# Tiny84_board.net
KiCad netlist of a schematic drawn in EAGLE
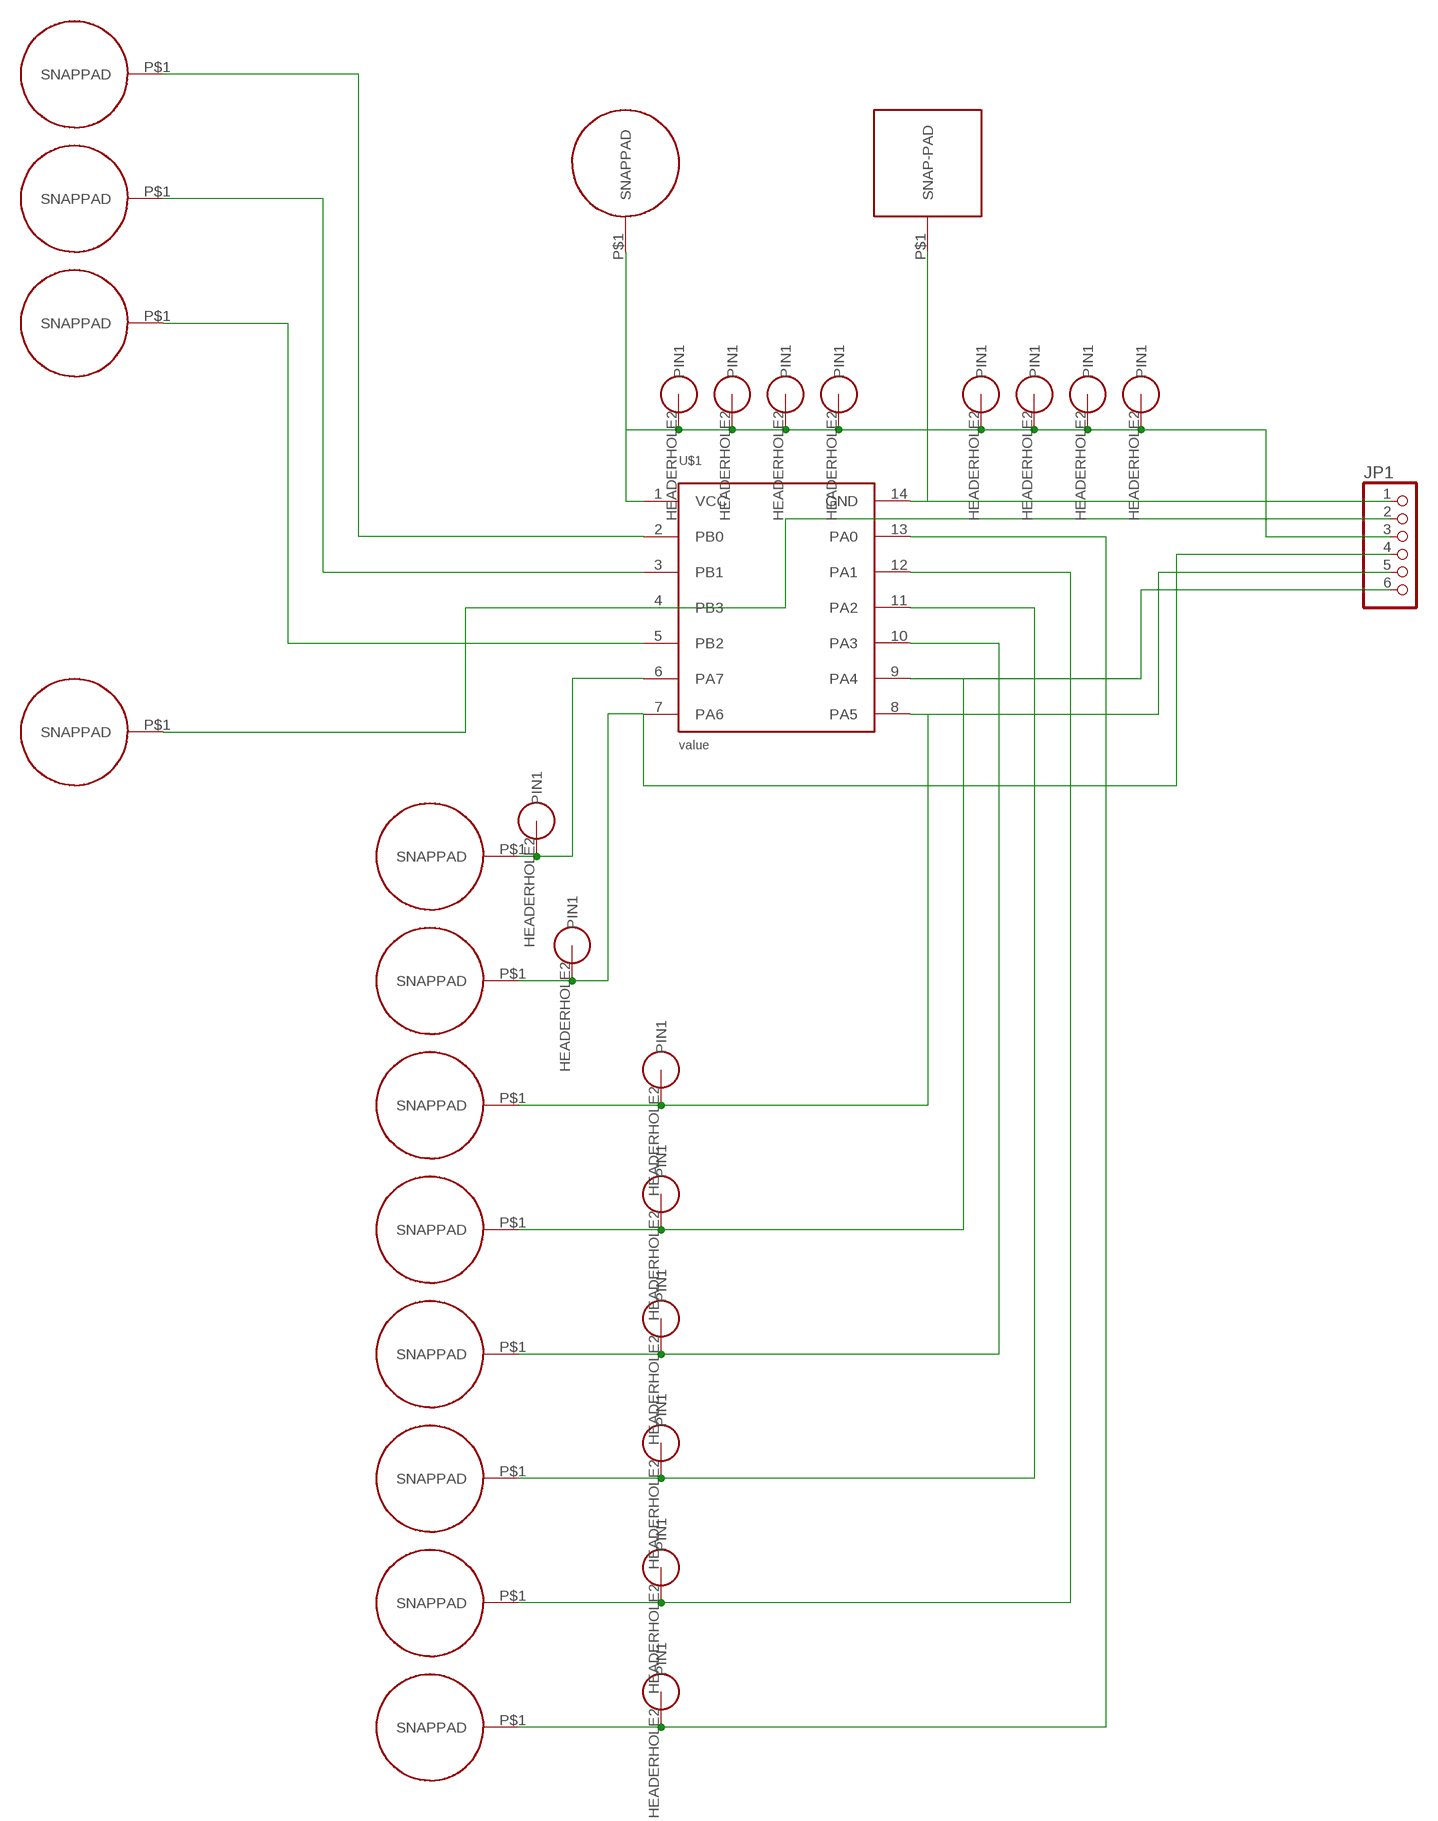
[diagram p0: schematic, sheet 1]

(export (version "E")
  (design (tool "Eeschema 10.0.6"))
  (components
    (comp (ref "JP1")
      (value "PINHD-1X6/90")
      (footprint "eagle-import:1X06_90")
      (libsource (lib "eagle-import") (part "PINHD-1X6/90"))
    )
    (comp (ref "U$1")
      (value "ATTINY84")
      (footprint "eagle-import:SOIC14")
      (libsource (lib "eagle-import") (part "ATTINY84"))
    )
    (comp (ref "U$2")
      (value "SNAP-PAD_7MM_ROUND")
      (footprint "eagle-import:SNAP-PAD_7MM_RD")
      (libsource (lib "eagle-import") (part "SNAP-PAD_7MM_ROUND"))
    )
    (comp (ref "U$3")
      (value "SNAP-PAD_7MM_ROUND")
      (footprint "eagle-import:SNAP-PAD_7MM_RD")
      (libsource (lib "eagle-import") (part "SNAP-PAD_7MM_ROUND"))
    )
    (comp (ref "U$4")
      (value "SNAP-PAD_7MM_ROUND")
      (footprint "eagle-import:SNAP-PAD_7MM_RD")
      (libsource (lib "eagle-import") (part "SNAP-PAD_7MM_ROUND"))
    )
    (comp (ref "U$5")
      (value "SNAP-PAD_7MM_ROUND")
      (footprint "eagle-import:SNAP-PAD_7MM_RD")
      (libsource (lib "eagle-import") (part "SNAP-PAD_7MM_ROUND"))
    )
    (comp (ref "U$6")
      (value "SNAP-PAD_7MM_ROUND")
      (footprint "eagle-import:SNAP-PAD_7MM_RD")
      (libsource (lib "eagle-import") (part "SNAP-PAD_7MM_ROUND"))
    )
    (comp (ref "U$7")
      (value "SNAP-PAD_7MM_ROUND")
      (footprint "eagle-import:SNAP-PAD_7MM_RD")
      (libsource (lib "eagle-import") (part "SNAP-PAD_7MM_ROUND"))
    )
    (comp (ref "U$8")
      (value "SNAP-PAD_7MM_ROUND")
      (footprint "eagle-import:SNAP-PAD_7MM_RD")
      (libsource (lib "eagle-import") (part "SNAP-PAD_7MM_ROUND"))
    )
    (comp (ref "U$9")
      (value "SNAP-PAD_7MM_ROUND")
      (footprint "eagle-import:SNAP-PAD_7MM_RD")
      (libsource (lib "eagle-import") (part "SNAP-PAD_7MM_ROUND"))
    )
    (comp (ref "U$10")
      (value "SNAP-PAD_7MM_ROUND")
      (footprint "eagle-import:SNAP-PAD_7MM_RD")
      (libsource (lib "eagle-import") (part "SNAP-PAD_7MM_ROUND"))
    )
    (comp (ref "U$11")
      (value "SNAP-PAD_7MM_ROUND")
      (footprint "eagle-import:SNAP-PAD_7MM_RD")
      (libsource (lib "eagle-import") (part "SNAP-PAD_7MM_ROUND"))
    )
    (comp (ref "U$12")
      (value "SNAP-PAD_7MM_ROUND")
      (footprint "eagle-import:SNAP-PAD_7MM_RD")
      (libsource (lib "eagle-import") (part "SNAP-PAD_7MM_ROUND"))
    )
    (comp (ref "U$13")
      (value "SNAP-PAD_7MM_ROUND")
      (footprint "eagle-import:SNAP-PAD_7MM_RD")
      (libsource (lib "eagle-import") (part "SNAP-PAD_7MM_ROUND"))
    )
    (comp (ref "U$14")
      (value "SNAP-PAD_7MM_SQUARE")
      (footprint "eagle-import:SNAP-PAD_7MM_SQ")
      (libsource (lib "eagle-import") (part "SNAP-PAD_7MM_SQUARE"))
    )
    (comp (ref "U$15")
      (value "HEADER_1PIN")
      (footprint "eagle-import:HEADER_1PIN")
      (libsource (lib "eagle-import") (part "HEADER_1PIN"))
    )
    (comp (ref "U$16")
      (value "HEADER_1PIN")
      (footprint "eagle-import:HEADER_1PIN")
      (libsource (lib "eagle-import") (part "HEADER_1PIN"))
    )
    (comp (ref "U$17")
      (value "HEADER_1PIN")
      (footprint "eagle-import:HEADER_1PIN")
      (libsource (lib "eagle-import") (part "HEADER_1PIN"))
    )
    (comp (ref "U$18")
      (value "SNAP-PAD_7MM_ROUND")
      (footprint "eagle-import:SNAP-PAD_7MM_RD")
      (libsource (lib "eagle-import") (part "SNAP-PAD_7MM_ROUND"))
    )
    (comp (ref "U$19")
      (value "HEADER_1PIN")
      (footprint "eagle-import:HEADER_1PIN")
      (libsource (lib "eagle-import") (part "HEADER_1PIN"))
    )
    (comp (ref "U$20")
      (value "HEADER_1PIN")
      (footprint "eagle-import:HEADER_1PIN")
      (libsource (lib "eagle-import") (part "HEADER_1PIN"))
    )
    (comp (ref "U$21")
      (value "HEADER_1PIN")
      (footprint "eagle-import:HEADER_1PIN")
      (libsource (lib "eagle-import") (part "HEADER_1PIN"))
    )
    (comp (ref "U$22")
      (value "HEADER_1PIN")
      (footprint "eagle-import:HEADER_1PIN")
      (libsource (lib "eagle-import") (part "HEADER_1PIN"))
    )
    (comp (ref "U$23")
      (value "HEADER_1PIN")
      (footprint "eagle-import:HEADER_1PIN")
      (libsource (lib "eagle-import") (part "HEADER_1PIN"))
    )
    (comp (ref "U$24")
      (value "HEADER_1PIN")
      (footprint "eagle-import:HEADER_1PIN")
      (libsource (lib "eagle-import") (part "HEADER_1PIN"))
    )
    (comp (ref "U$25")
      (value "HEADER_1PIN")
      (footprint "eagle-import:HEADER_1PIN")
      (libsource (lib "eagle-import") (part "HEADER_1PIN"))
    )
    (comp (ref "U$26")
      (value "HEADER_1PIN")
      (footprint "eagle-import:HEADER_1PIN")
      (libsource (lib "eagle-import") (part "HEADER_1PIN"))
    )
    (comp (ref "U$27")
      (value "HEADER_1PIN")
      (footprint "eagle-import:HEADER_1PIN")
      (libsource (lib "eagle-import") (part "HEADER_1PIN"))
    )
    (comp (ref "U$28")
      (value "HEADER_1PIN")
      (footprint "eagle-import:HEADER_1PIN")
      (libsource (lib "eagle-import") (part "HEADER_1PIN"))
    )
    (comp (ref "U$29")
      (value "HEADER_1PIN")
      (footprint "eagle-import:HEADER_1PIN")
      (libsource (lib "eagle-import") (part "HEADER_1PIN"))
    )
    (comp (ref "U$30")
      (value "HEADER_1PIN")
      (footprint "eagle-import:HEADER_1PIN")
      (libsource (lib "eagle-import") (part "HEADER_1PIN"))
    )
    (comp (ref "U$31")
      (value "HEADER_1PIN")
      (footprint "eagle-import:HEADER_1PIN")
      (libsource (lib "eagle-import") (part "HEADER_1PIN"))
    )
  )
  (nets
    (net (code "1") (name "Net-(U$1-GND)") (class "Default")
      (node (ref "JP1") (pin "1") (pinfunction "1_1") (pintype "passive"))
      (node (ref "U$1") (pin "14") (pinfunction "GND_14") (pintype "bidirectional"))
      (node (ref "U$14") (pin "P$1") (pinfunction "SNAP-PAD_P$1") (pintype "bidirectional"))
    )
    (net (code "2") (name "Net-(U$1-PA0)") (class "Default")
      (node (ref "U$1") (pin "13") (pinfunction "PA0_13") (pintype "bidirectional"))
      (node (ref "U$23") (pin "HEADERHOLE2") (pinfunction "PIN1_HEADERHOLE2") (pintype "bidirectional"))
      (node (ref "U$9") (pin "P$1") (pinfunction "SNAPPAD_P$1") (pintype "bidirectional"))
    )
    (net (code "3") (name "Net-(U$1-PA1)") (class "Default")
      (node (ref "U$1") (pin "12") (pinfunction "PA1_12") (pintype "bidirectional"))
      (node (ref "U$22") (pin "HEADERHOLE2") (pinfunction "PIN1_HEADERHOLE2") (pintype "bidirectional"))
      (node (ref "U$8") (pin "P$1") (pinfunction "SNAPPAD_P$1") (pintype "bidirectional"))
    )
    (net (code "4") (name "Net-(U$1-PA2)") (class "Default")
      (node (ref "U$1") (pin "11") (pinfunction "PA2_11") (pintype "bidirectional"))
      (node (ref "U$21") (pin "HEADERHOLE2") (pinfunction "PIN1_HEADERHOLE2") (pintype "bidirectional"))
      (node (ref "U$7") (pin "P$1") (pinfunction "SNAPPAD_P$1") (pintype "bidirectional"))
    )
    (net (code "5") (name "Net-(U$1-PA3)") (class "Default")
      (node (ref "U$1") (pin "10") (pinfunction "PA3_10") (pintype "bidirectional"))
      (node (ref "U$20") (pin "HEADERHOLE2") (pinfunction "PIN1_HEADERHOLE2") (pintype "bidirectional"))
      (node (ref "U$6") (pin "P$1") (pinfunction "SNAPPAD_P$1") (pintype "bidirectional"))
    )
    (net (code "6") (name "Net-(U$1-PA4)") (class "Default")
      (node (ref "JP1") (pin "6") (pinfunction "6_6") (pintype "passive"))
      (node (ref "U$1") (pin "9") (pinfunction "PA4_9") (pintype "bidirectional"))
      (node (ref "U$19") (pin "HEADERHOLE2") (pinfunction "PIN1_HEADERHOLE2") (pintype "bidirectional"))
      (node (ref "U$5") (pin "P$1") (pinfunction "SNAPPAD_P$1") (pintype "bidirectional"))
    )
    (net (code "7") (name "Net-(U$1-PA5)") (class "Default")
      (node (ref "JP1") (pin "5") (pinfunction "5_5") (pintype "passive"))
      (node (ref "U$1") (pin "8") (pinfunction "PA5_8") (pintype "bidirectional"))
      (node (ref "U$17") (pin "HEADERHOLE2") (pinfunction "PIN1_HEADERHOLE2") (pintype "bidirectional"))
      (node (ref "U$4") (pin "P$1") (pinfunction "SNAPPAD_P$1") (pintype "bidirectional"))
    )
    (net (code "8") (name "Net-(U$1-PA6)") (class "Default")
      (node (ref "JP1") (pin "4") (pinfunction "4_4") (pintype "passive"))
      (node (ref "U$1") (pin "7") (pinfunction "PA6_7") (pintype "bidirectional"))
      (node (ref "U$26") (pin "HEADERHOLE2") (pinfunction "PIN1_HEADERHOLE2") (pintype "bidirectional"))
      (node (ref "U$3") (pin "P$1") (pinfunction "SNAPPAD_P$1") (pintype "bidirectional"))
    )
    (net (code "9") (name "Net-(U$1-PA7)") (class "Default")
      (node (ref "U$1") (pin "6") (pinfunction "PA7_6") (pintype "bidirectional"))
      (node (ref "U$2") (pin "P$1") (pinfunction "SNAPPAD_P$1") (pintype "bidirectional"))
      (node (ref "U$27") (pin "HEADERHOLE2") (pinfunction "PIN1_HEADERHOLE2") (pintype "bidirectional"))
    )
    (net (code "10") (name "Net-(U$1-PB0)") (class "Default")
      (node (ref "U$1") (pin "2") (pinfunction "PB0_2") (pintype "bidirectional"))
      (node (ref "U$11") (pin "P$1") (pinfunction "SNAPPAD_P$1") (pintype "bidirectional"))
    )
    (net (code "11") (name "Net-(U$1-PB1)") (class "Default")
      (node (ref "U$1") (pin "3") (pinfunction "PB1_3") (pintype "bidirectional"))
      (node (ref "U$12") (pin "P$1") (pinfunction "SNAPPAD_P$1") (pintype "bidirectional"))
    )
    (net (code "12") (name "Net-(U$1-PB2)") (class "Default")
      (node (ref "U$1") (pin "5") (pinfunction "PB2_5") (pintype "bidirectional"))
      (node (ref "U$13") (pin "P$1") (pinfunction "SNAPPAD_P$1") (pintype "bidirectional"))
    )
    (net (code "13") (name "Net-(U$1-PB3)") (class "Default")
      (node (ref "JP1") (pin "2") (pinfunction "2_2") (pintype "passive"))
      (node (ref "U$1") (pin "4") (pinfunction "PB3_4") (pintype "bidirectional"))
      (node (ref "U$18") (pin "P$1") (pinfunction "SNAPPAD_P$1") (pintype "bidirectional"))
    )
    (net (code "14") (name "Net-(U$1-VCC)") (class "Default")
      (node (ref "JP1") (pin "3") (pinfunction "3_3") (pintype "passive"))
      (node (ref "U$1") (pin "1") (pinfunction "VCC_1") (pintype "bidirectional"))
      (node (ref "U$10") (pin "P$1") (pinfunction "SNAPPAD_P$1") (pintype "bidirectional"))
      (node (ref "U$15") (pin "HEADERHOLE2") (pinfunction "PIN1_HEADERHOLE2") (pintype "bidirectional"))
      (node (ref "U$16") (pin "HEADERHOLE2") (pinfunction "PIN1_HEADERHOLE2") (pintype "bidirectional"))
      (node (ref "U$24") (pin "HEADERHOLE2") (pinfunction "PIN1_HEADERHOLE2") (pintype "bidirectional"))
      (node (ref "U$25") (pin "HEADERHOLE2") (pinfunction "PIN1_HEADERHOLE2") (pintype "bidirectional"))
      (node (ref "U$28") (pin "HEADERHOLE2") (pinfunction "PIN1_HEADERHOLE2") (pintype "bidirectional"))
      (node (ref "U$29") (pin "HEADERHOLE2") (pinfunction "PIN1_HEADERHOLE2") (pintype "bidirectional"))
      (node (ref "U$30") (pin "HEADERHOLE2") (pinfunction "PIN1_HEADERHOLE2") (pintype "bidirectional"))
      (node (ref "U$31") (pin "HEADERHOLE2") (pinfunction "PIN1_HEADERHOLE2") (pintype "bidirectional"))
    )
  )
)
